# LEM.net
KiCad netlist of a schematic drawn in Altium Designer
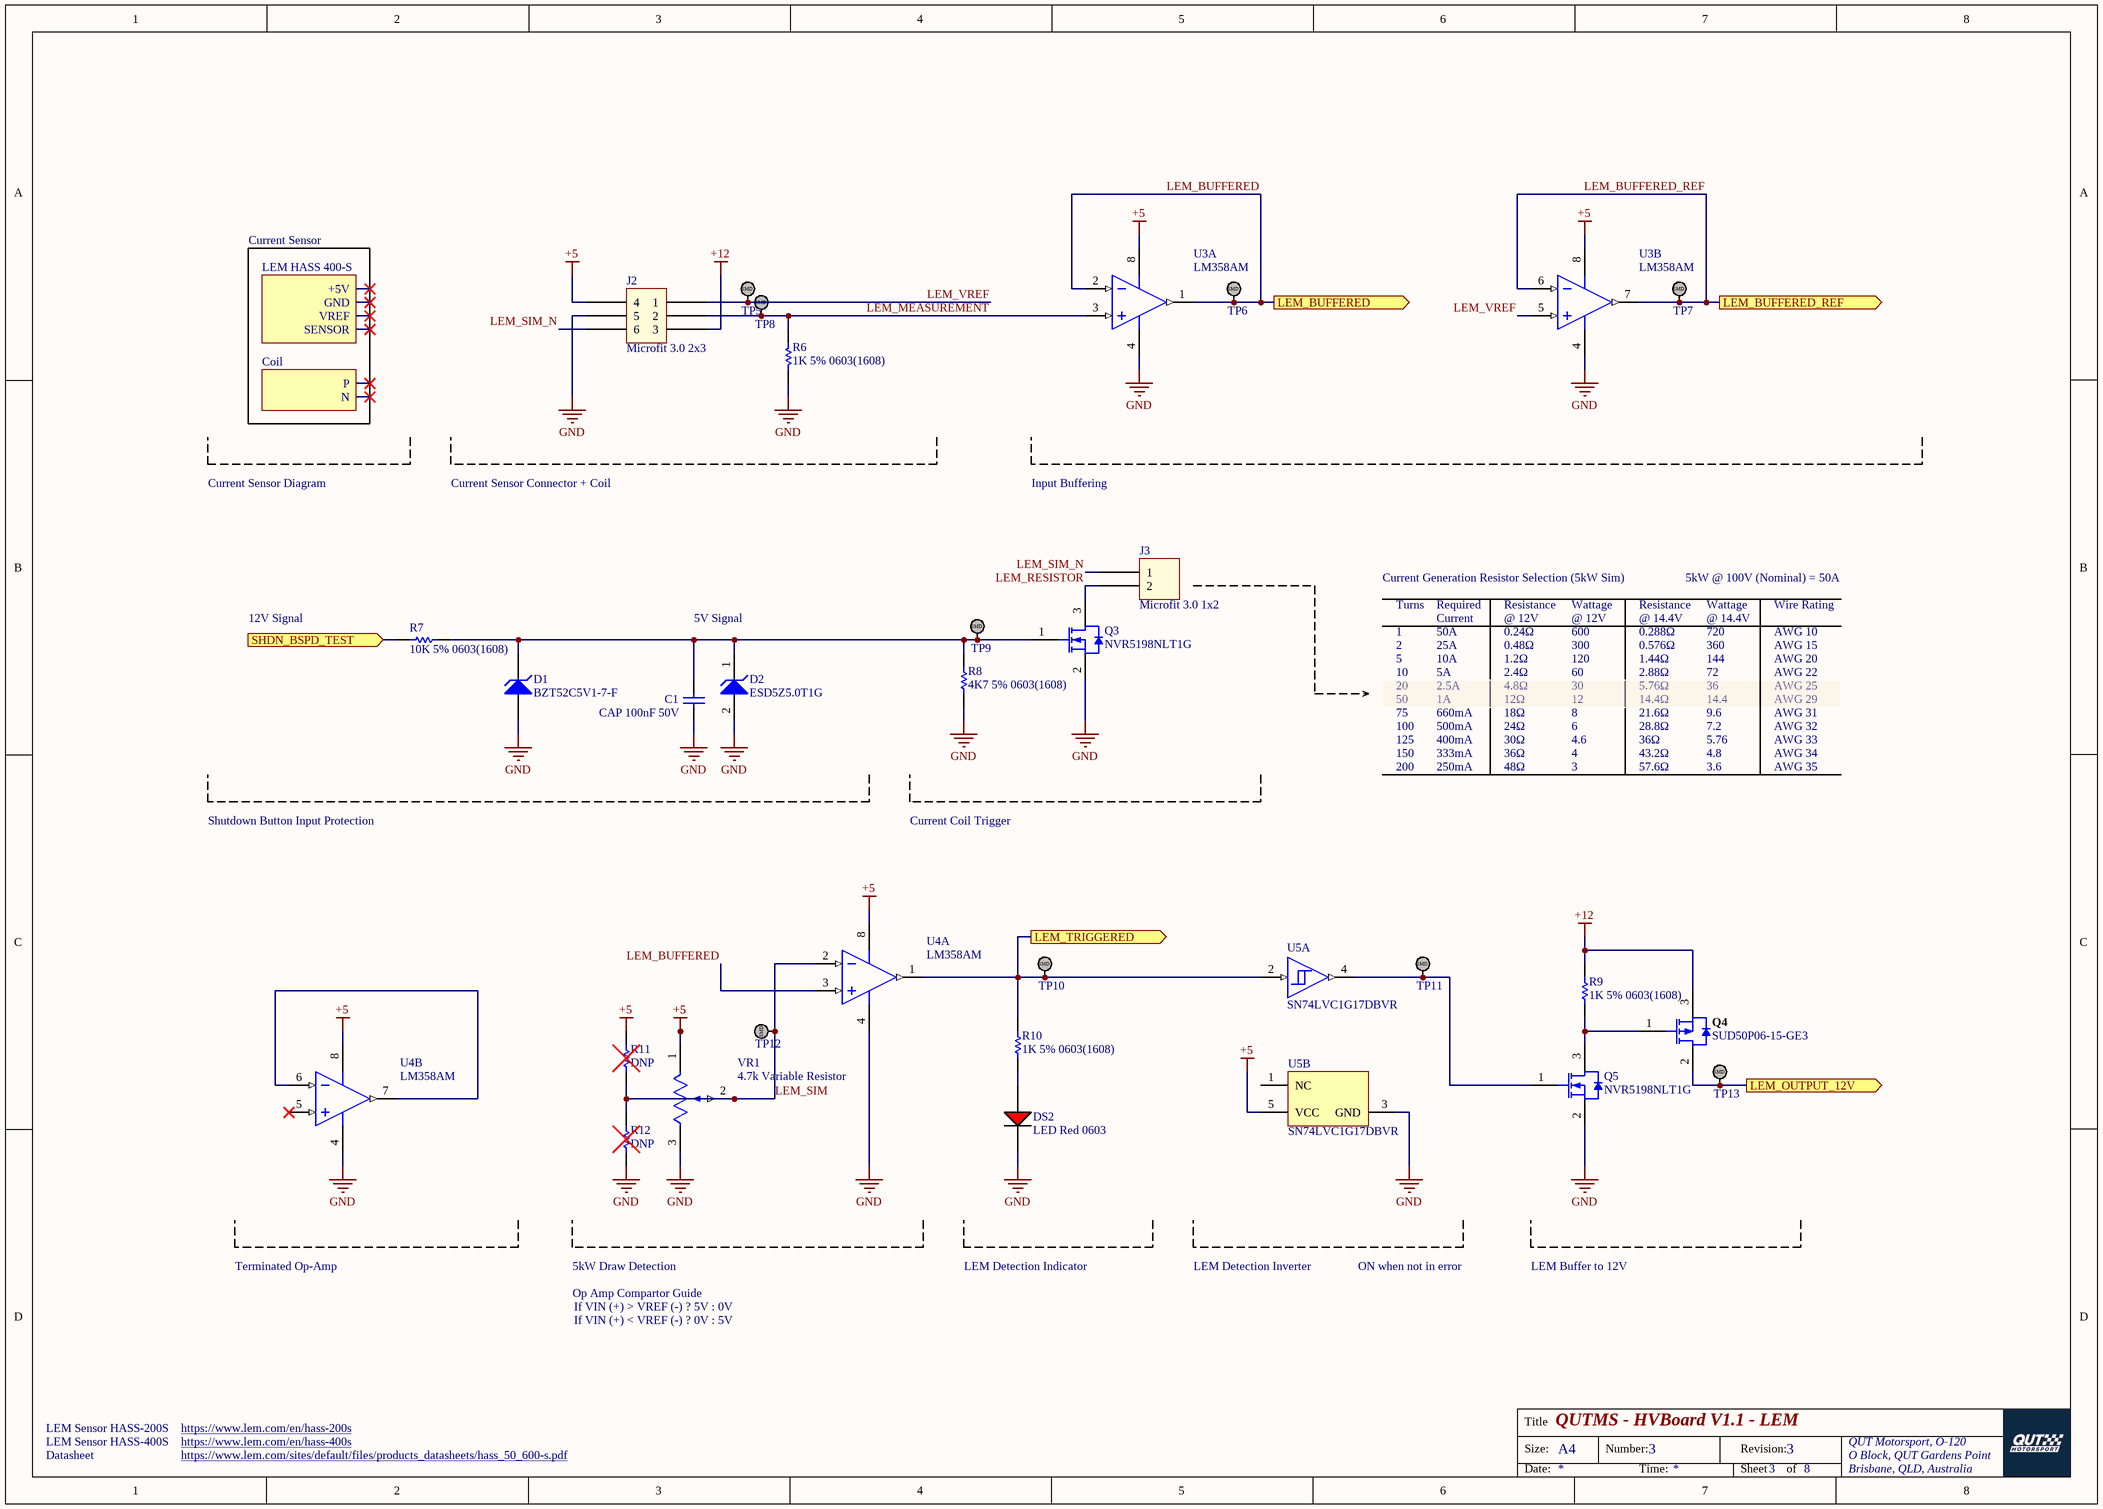
[diagram p0: LEM.SchDoc]

(export (version "E")
  (design (tool "Eeschema 10.0.6"))
  (components
    (comp (ref "C1")
      (value "CAP 100nF 50V")
      (footprint "CAPC0603(1608)100_L")
      (description "CAP 100nF 50V ±5% 0603 (1608 Metric) Thickness 1mm SMD")
      (fields (field (name "TOLERANCE") "Â±5%"))
      (libsource (lib "Altium Content Vault") (part "CAP"))
    )
    (comp (ref "D1")
      (value "BZT52C5V1-7-F")
      (footprint "DIOD-SOD123_V")
      (description "Surface Mount Zener Diode, 5.1 V, -65 to 150 degC, 2-Pin SMD (SOD-123), RoHS, Tape and Reel")
      (fields (field (name "MANUFACTURER") "DiodesIncorporated"))
      (libsource (lib "Altium Content Vault") (part "DZEN-AK-2"))
    )
    (comp (ref "D2")
      (value "ESD5Z5.0T1G")
      (footprint "ONSC-SOD-523-2-502-01_V")
      (fields (field (name "MANUFACTURER") "On Semiconductor"))
      (libsource (lib "Altium Content Vault") (part "ONSC-K1A2-2"))
    )
    (comp (ref "DS2")
      (value "LED Red 0603")
      (footprint "LED RED 0603")
      (libsource (lib "QUTMS_LEDLibrary") (part "LED RED 0603"))
    )
    (comp (ref "J2")
      (value "Microfit 3.0 2x3")
      (footprint "Microfit_2X3_R_TH")
      (libsource (lib "QUTMS_Microfit") (part "Microfit_2x3"))
    )
    (comp (ref "J3")
      (value "Microfit 3.0 1x2")
      (footprint "Microfit_1X2_R_TH")
      (libsource (lib "QUTMS_Microfit") (part "Microfit_1x2"))
    )
    (comp (ref "Q3")
      (value "NVR5198NLT1G")
      (footprint "ONSC-SOT-23-3-318-08_V")
      (description "Power MOSFET, 60 V, 155 mOhm, Single N-Channel Logic Level, 3-Pin SOT-23, Pb-Free, Tape and Reel")
      (fields (field (name "MANUFACTURER") "On Semiconductor"))
      (libsource (lib "Altium Content Vault") (part "ONSC-NMOS-G1S2D3-3"))
    )
    (comp (ref "Q4")
      (value "SUD50P06-15-GE3")
      (footprint "VSIL-TO-252AA-3_V")
      (description "P-Channel (D-S) MOSFET, 30 V, -55 to 150 degC, 3-Pin TO-252, RoHS, Tape and Reel")
      (fields (field (name "MANUFACTURER") "Vishay"))
      (libsource (lib "Altium Content Vault") (part "PEMOS-GDS-3"))
    )
    (comp (ref "Q5")
      (value "NVR5198NLT1G")
      (footprint "ONSC-SOT-23-3-318-08_V")
      (description "Power MOSFET, 60 V, 155 mOhm, Single N-Channel Logic Level, 3-Pin SOT-23, Pb-Free, Tape and Reel")
      (fields (field (name "MANUFACTURER") "On Semiconductor"))
      (libsource (lib "Altium Content Vault") (part "ONSC-NMOS-G1S2D3-3"))
    )
    (comp (ref "R6")
      (value "1K 5% 0603(1608)")
      (footprint "RESC0603(1608)_L")
      (description "1K 0.1W 5% 0603 (1608 Metric)  SMD")
      (fields (field (name "TOLERANCE") "5 %") (field (name "POWER") "0.1 W"))
      (libsource (lib "Altium Content Vault") (part "RES"))
    )
    (comp (ref "R7")
      (value "10K 5% 0603(1608)")
      (footprint "RESC0603(1608)_N")
      (description "10K 0.1W 5% 0603 (1608 Metric)  SMD")
      (fields (field (name "TOLERANCE") "5 %") (field (name "POWER") "0.1 W"))
      (libsource (lib "Altium Content Vault") (part "RES"))
    )
    (comp (ref "R8")
      (value "4K7 5% 0603(1608)")
      (footprint "RESC0603(1608)_N")
      (description "4K7 0.1W 5% 0603 (1608 Metric)  SMD")
      (fields (field (name "TOLERANCE") "5 %") (field (name "POWER") "0.1 W"))
      (libsource (lib "Altium Content Vault") (part "RES"))
    )
    (comp (ref "R9")
      (value "1K 5% 0603(1608)")
      (footprint "RESC0603(1608)_L")
      (description "1K 0.1W 5% 0603 (1608 Metric)  SMD")
      (fields (field (name "TOLERANCE") "5 %") (field (name "POWER") "0.1 W"))
      (libsource (lib "Altium Content Vault") (part "RES"))
    )
    (comp (ref "R10")
      (value "1K 5% 0603(1608)")
      (footprint "RESC0603(1608)_L")
      (description "1K 0.1W 5% 0603 (1608 Metric)  SMD")
      (fields (field (name "TOLERANCE") "5 %") (field (name "POWER") "0.1 W"))
      (libsource (lib "Altium Content Vault") (part "RES"))
    )
    (comp (ref "R11")
      (value "DNP")
      (footprint "RESC0603(1608)_L")
      (description "0603 (1608 Metric) Chip Resistor")
      (libsource (lib "Altium Content Vault") (part "RES_3"))
    )
    (comp (ref "R12")
      (value "DNP")
      (footprint "RESC0603(1608)_L")
      (description "0603 (1608 Metric) Chip Resistor")
      (libsource (lib "Altium Content Vault") (part "RES_3"))
    )
    (comp (ref "TP5")
      (value "TestPoint_SMD")
      (footprint "TestPointSMD")
      (libsource (lib "StandardTest") (part "TestPoint_SMD"))
    )
    (comp (ref "TP6")
      (value "TestPoint_SMD")
      (footprint "TestPointSMD")
      (libsource (lib "StandardTest") (part "TestPoint_SMD"))
    )
    (comp (ref "TP7")
      (value "TestPoint_SMD")
      (footprint "TestPointSMD")
      (libsource (lib "StandardTest") (part "TestPoint_SMD"))
    )
    (comp (ref "TP8")
      (value "TestPoint_SMD")
      (footprint "TestPointSMD")
      (libsource (lib "StandardTest") (part "TestPoint_SMD"))
    )
    (comp (ref "TP9")
      (value "TestPoint_SMD")
      (footprint "TestPointSMD")
      (libsource (lib "StandardTest") (part "TestPoint_SMD"))
    )
    (comp (ref "TP10")
      (value "TestPoint_SMD")
      (footprint "TestPointSMD")
      (libsource (lib "StandardTest") (part "TestPoint_SMD"))
    )
    (comp (ref "TP11")
      (value "TestPoint_SMD")
      (footprint "TestPointSMD")
      (libsource (lib "StandardTest") (part "TestPoint_SMD"))
    )
    (comp (ref "TP12")
      (value "TestPoint_SMD")
      (footprint "TestPointSMD")
      (libsource (lib "StandardTest") (part "TestPoint_SMD"))
    )
    (comp (ref "TP13")
      (value "TestPoint_SMD")
      (footprint "TestPointSMD")
      (libsource (lib "StandardTest") (part "TestPoint_SMD"))
    )
    (comp (ref "U3")
      (value "LM358AM")
      (footprint "D0008A_N")
      (description "Low Power Dual Operational Amplifier, 8-pin Narrow SOIC")
      (fields (field (name "MANUFACTURER") "Texas Instruments"))
      (libsource (lib "Altium Content Vault") (part "AMP-OPA-LM158-8"))
    )
    (comp (ref "U4")
      (value "LM358AM")
      (footprint "D0008A_N")
      (description "Low Power Dual Operational Amplifier, 8-pin Narrow SOIC")
      (fields (field (name "MANUFACTURER") "Texas Instruments"))
      (libsource (lib "Altium Content Vault") (part "AMP-OPA-LM158-8"))
    )
    (comp (ref "U5")
      (value "SN74LVC1G17DBVR")
      (footprint "DBV0005A_L")
      (description "Single Schmitt-Trigger Buffer, DBV0005A, LARGE T&R")
      (fields
        (field (name "MANUFACTURER") "Texas Instruments")
        (field (name "GENERIC PART NUMBER") "SN74LVC1G17")
      )
      (libsource (lib "Altium Content Vault") (part "TI-SN74XXX1XXX-XX-5-SCHMITT"))
    )
    (comp (ref "VR1")
      (value "4.7k Variable Resistor")
      (footprint "VG039NCHXTB472")
      (description "4k7 ±25% ±250 ppm/°C SMD Variable Resistors RoHS ¦ VG039NCHXTB472")
      (libsource (lib "QUTMS_PotentiometerLibrary") (part "4.7k Variable Resistor"))
    )
  )
  (nets
    (net (code "1") (name "+5") (class "Default")
      (node (ref "J2") (pin "4") (pinfunction "4_4") (pintype "passive"))
      (node (ref "R11") (pin "2") (pinfunction "2_2") (pintype "passive"))
      (node (ref "U3") (pin "8") (pinfunction "V+_8") (pintype "power_in"))
      (node (ref "U4") (pin "8") (pinfunction "V+_8") (pintype "power_in"))
      (node (ref "U5") (pin "5") (pinfunction "VCC_5") (pintype "power_in"))
      (node (ref "VR1") (pin "1") (pinfunction "48_1") (pintype "passive"))
    )
    (net (code "2") (name "+12") (class "Default")
      (node (ref "J2") (pin "3") (pinfunction "3_3") (pintype "passive"))
      (node (ref "Q4") (pin "3") (pinfunction "S_3") (pintype "passive"))
      (node (ref "R9") (pin "2") (pinfunction "2_2") (pintype "passive"))
    )
    (net (code "3") (name "/LEM_BUFFERED") (class "Default")
      (node (ref "TP6") (pin "1") (pinfunction "1_1") (pintype "passive"))
      (node (ref "U3") (pin "1") (pinfunction "OUTA_1") (pintype "output"))
      (node (ref "U3") (pin "2") (pinfunction "INA-_2") (pintype "input"))
      (node (ref "U4") (pin "3") (pinfunction "INA+_3") (pintype "input"))
    )
    (net (code "4") (name "/LEM_BUFFERED_REF") (class "Default")
      (node (ref "TP7") (pin "1") (pinfunction "1_1") (pintype "passive"))
      (node (ref "U3") (pin "6") (pinfunction "INB-_6") (pintype "input"))
      (node (ref "U3") (pin "7") (pinfunction "OUTB_7") (pintype "output"))
    )
    (net (code "5") (name "/LEM_MEASUREMENT") (class "Default")
      (node (ref "J2") (pin "2") (pinfunction "2_2") (pintype "passive"))
      (node (ref "R6") (pin "2") (pinfunction "2_2") (pintype "passive"))
      (node (ref "TP8") (pin "1") (pinfunction "1_1") (pintype "passive"))
      (node (ref "U3") (pin "3") (pinfunction "INA+_3") (pintype "input"))
    )
    (net (code "6") (name "/LEM_OUTPUT_12V") (class "Default")
      (node (ref "Q4") (pin "2") (pinfunction "D_2") (pintype "passive"))
      (node (ref "TP13") (pin "1") (pinfunction "1_1") (pintype "passive"))
    )
    (net (code "7") (name "/LEM_RESISTOR") (class "Default")
      (node (ref "J3") (pin "2") (pinfunction "2_2") (pintype "passive"))
      (node (ref "Q3") (pin "3") (pinfunction "D_3") (pintype "passive"))
    )
    (net (code "8") (name "/LEM_SIM") (class "Default")
      (node (ref "R11") (pin "1") (pinfunction "1_1") (pintype "passive"))
      (node (ref "R12") (pin "2") (pinfunction "2_2") (pintype "passive"))
      (node (ref "TP12") (pin "1") (pinfunction "1_1") (pintype "passive"))
      (node (ref "U4") (pin "2") (pinfunction "INA-_2") (pintype "input"))
      (node (ref "VR1") (pin "2") (pinfunction "50_2") (pintype "output"))
    )
    (net (code "9") (name "/LEM_SIM_N") (class "Default")
      (node (ref "J2") (pin "6") (pinfunction "6_6") (pintype "passive"))
      (node (ref "J3") (pin "1") (pinfunction "1_1") (pintype "passive"))
    )
    (net (code "10") (name "/LEM_TRIGGERED") (class "Default")
      (node (ref "R10") (pin "2") (pinfunction "2_2") (pintype "passive"))
      (node (ref "TP10") (pin "1") (pinfunction "1_1") (pintype "passive"))
      (node (ref "U4") (pin "1") (pinfunction "OUTA_1") (pintype "output"))
      (node (ref "U5") (pin "2") (pinfunction "A_2") (pintype "input"))
    )
    (net (code "11") (name "/LEM_VREF") (class "Default")
      (node (ref "J2") (pin "1") (pinfunction "1_1") (pintype "passive"))
      (node (ref "TP5") (pin "1") (pinfunction "1_1") (pintype "passive"))
      (node (ref "U3") (pin "5") (pinfunction "INB+_5") (pintype "input"))
    )
    (net (code "12") (name "/SHDN_BSPD_TEST") (class "Default")
      (node (ref "R7") (pin "2") (pinfunction "2_2") (pintype "passive"))
    )
    (net (code "13") (name "GND") (class "Default")
      (node (ref "C1") (pin "2") (pinfunction "2_2") (pintype "passive"))
      (node (ref "D1") (pin "1") (pinfunction "A_1") (pintype "passive"))
      (node (ref "D2") (pin "2") (pinfunction "A_2") (pintype "passive"))
      (node (ref "DS2") (pin "2") (pinfunction "C_2") (pintype "passive"))
      (node (ref "J2") (pin "5") (pinfunction "5_5") (pintype "passive"))
      (node (ref "Q3") (pin "2") (pinfunction "S_2") (pintype "passive"))
      (node (ref "Q5") (pin "2") (pinfunction "S_2") (pintype "passive"))
      (node (ref "R12") (pin "1") (pinfunction "1_1") (pintype "passive"))
      (node (ref "R6") (pin "1") (pinfunction "1_1") (pintype "passive"))
      (node (ref "R8") (pin "1") (pinfunction "1_1") (pintype "passive"))
      (node (ref "U3") (pin "4") (pinfunction "GND_4") (pintype "power_in"))
      (node (ref "U4") (pin "4") (pinfunction "GND_4") (pintype "power_in"))
      (node (ref "U5") (pin "3") (pinfunction "GND_3") (pintype "power_in"))
      (node (ref "VR1") (pin "3") (pinfunction "49_3") (pintype "passive"))
    )
    (net (code "14") (name "Net-(D1-K)") (class "Default")
      (node (ref "C1") (pin "1") (pinfunction "1_1") (pintype "passive"))
      (node (ref "D1") (pin "2") (pinfunction "K_2") (pintype "passive"))
      (node (ref "D2") (pin "1") (pinfunction "K_1") (pintype "passive"))
      (node (ref "Q3") (pin "1") (pinfunction "G_1") (pintype "passive"))
      (node (ref "R7") (pin "1") (pinfunction "1_1") (pintype "passive"))
      (node (ref "R8") (pin "2") (pinfunction "2_2") (pintype "passive"))
      (node (ref "TP9") (pin "1") (pinfunction "1_1") (pintype "passive"))
    )
    (net (code "15") (name "Net-(DS2-A)") (class "Default")
      (node (ref "DS2") (pin "1") (pinfunction "A_1") (pintype "passive"))
      (node (ref "R10") (pin "1") (pinfunction "1_1") (pintype "passive"))
    )
    (net (code "16") (name "Net-(Q4-G)") (class "Default")
      (node (ref "Q4") (pin "1") (pinfunction "G_1") (pintype "passive"))
      (node (ref "Q5") (pin "3") (pinfunction "D_3") (pintype "passive"))
      (node (ref "R9") (pin "1") (pinfunction "1_1") (pintype "passive"))
    )
    (net (code "17") (name "Net-(Q5-G)") (class "Default")
      (node (ref "Q5") (pin "1") (pinfunction "G_1") (pintype "passive"))
      (node (ref "TP11") (pin "1") (pinfunction "1_1") (pintype "passive"))
      (node (ref "U5") (pin "4") (pinfunction "Y_4") (pintype "output"))
    )
    (net (code "18") (name "Net-(U4B-INB-)") (class "Default")
      (node (ref "U4") (pin "6") (pinfunction "INB-_6") (pintype "input"))
      (node (ref "U4") (pin "7") (pinfunction "OUTB_7") (pintype "output"))
    )
    (net (code "19") (name "unconnected-(U4B-INB+-Pad5)") (class "Default")
      (node (ref "U4") (pin "5") (pinfunction "INB+_5") (pintype "input+no_connect"))
    )
    (net (code "20") (name "unconnected-(U5B-NC-Pad1)") (class "Default")
      (node (ref "U5") (pin "1") (pinfunction "NC_1") (pintype "passive"))
    )
  )
)
